# ALU_Connector.net
KiCad netlist of a schematic drawn in Altium Designer
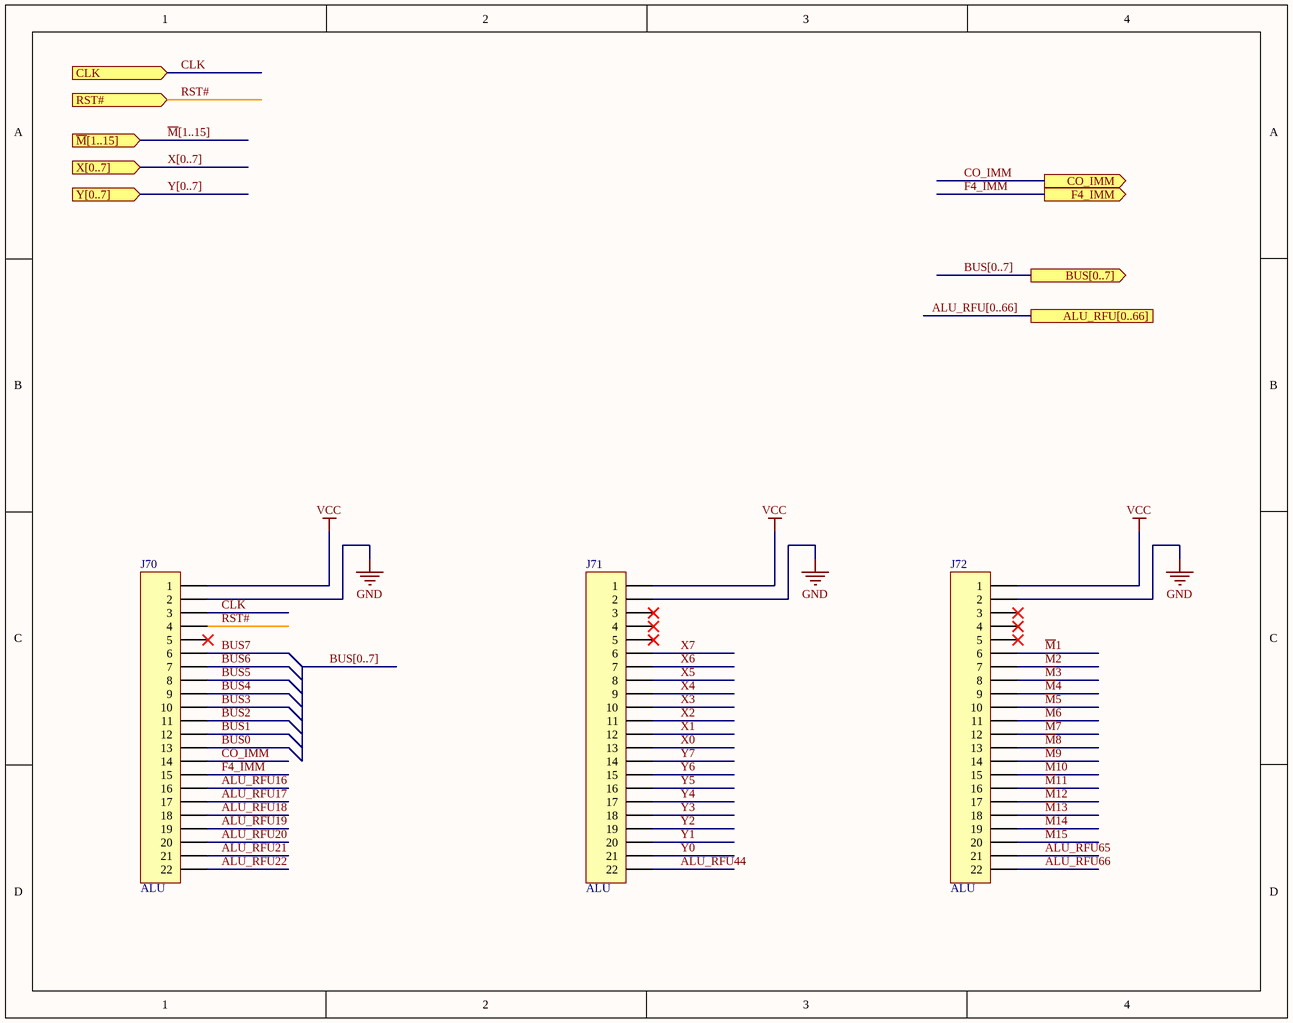
[diagram p0: ALU Connector.SchDoc]

(export (version "E")
  (design (tool "Eeschema 10.0.6"))
  (components
    (comp (ref "J70")
      (value "ALU")
      (footprint "HDR1X22")
      (description "Header, 22-Pin")
      (fields (field (name "PUBLISHER") "Altium Limited"))
      (libsource (lib "Miscellaneous Connectors") (part "Header 22"))
    )
    (comp (ref "J71")
      (value "ALU")
      (footprint "HDR1X22")
      (description "Header, 22-Pin")
      (fields (field (name "PUBLISHER") "Altium Limited"))
      (libsource (lib "Miscellaneous Connectors") (part "Header 22"))
    )
    (comp (ref "J72")
      (value "ALU")
      (footprint "HDR1X22")
      (description "Header, 22-Pin")
      (fields (field (name "PUBLISHER") "Altium Limited"))
      (libsource (lib "Miscellaneous Connectors") (part "Header 22"))
    )
  )
  (nets
    (net (code "58") (name "/ALU_RFU16") (class "Default")
      (node (ref "J70") (pin "16") (pinfunction "16_16") (pintype "passive"))
    )
    (net (code "59") (name "/ALU_RFU17") (class "Default")
      (node (ref "J70") (pin "17") (pinfunction "17_17") (pintype "passive"))
    )
    (net (code "60") (name "/ALU_RFU18") (class "Default")
      (node (ref "J70") (pin "18") (pinfunction "18_18") (pintype "passive"))
    )
    (net (code "61") (name "/ALU_RFU19") (class "Default")
      (node (ref "J70") (pin "19") (pinfunction "19_19") (pintype "passive"))
    )
    (net (code "62") (name "/ALU_RFU20") (class "Default")
      (node (ref "J70") (pin "20") (pinfunction "20_20") (pintype "passive"))
    )
    (net (code "63") (name "/ALU_RFU21") (class "Default")
      (node (ref "J70") (pin "21") (pinfunction "21_21") (pintype "passive"))
    )
    (net (code "64") (name "/ALU_RFU22") (class "Default")
      (node (ref "J70") (pin "22") (pinfunction "22_22") (pintype "passive"))
    )
    (net (code "65") (name "/ALU_RFU44") (class "Default")
      (node (ref "J71") (pin "22") (pinfunction "22_22") (pintype "passive"))
    )
    (net (code "66") (name "/ALU_RFU65") (class "Default")
      (node (ref "J72") (pin "21") (pinfunction "21_21") (pintype "passive"))
    )
    (net (code "67") (name "/ALU_RFU66") (class "Default")
      (node (ref "J72") (pin "22") (pinfunction "22_22") (pintype "passive"))
    )
    (net (code "69") (name "/BUS0") (class "Default")
      (node (ref "J70") (pin "13") (pinfunction "13_13") (pintype "passive"))
    )
    (net (code "70") (name "/BUS1") (class "Default")
      (node (ref "J70") (pin "12") (pinfunction "12_12") (pintype "passive"))
    )
    (net (code "71") (name "/BUS2") (class "Default")
      (node (ref "J70") (pin "11") (pinfunction "11_11") (pintype "passive"))
    )
    (net (code "72") (name "/BUS3") (class "Default")
      (node (ref "J70") (pin "10") (pinfunction "10_10") (pintype "passive"))
    )
    (net (code "73") (name "/BUS4") (class "Default")
      (node (ref "J70") (pin "9") (pinfunction "9_9") (pintype "passive"))
    )
    (net (code "74") (name "/BUS5") (class "Default")
      (node (ref "J70") (pin "8") (pinfunction "8_8") (pintype "passive"))
    )
    (net (code "75") (name "/BUS6") (class "Default")
      (node (ref "J70") (pin "7") (pinfunction "7_7") (pintype "passive"))
    )
    (net (code "76") (name "/BUS7") (class "Default")
      (node (ref "J70") (pin "6") (pinfunction "6_6") (pintype "passive"))
    )
    (net (code "78") (name "/CLK") (class "Default")
      (node (ref "J70") (pin "3") (pinfunction "3_3") (pintype "passive"))
    )
    (net (code "79") (name "/CO_IMM") (class "Default")
      (node (ref "J70") (pin "14") (pinfunction "14_14") (pintype "passive"))
    )
    (net (code "80") (name "/F4_IMM") (class "Default")
      (node (ref "J70") (pin "15") (pinfunction "15_15") (pintype "passive"))
    )
    (net (code "81") (name "/RST#") (class "Default")
      (node (ref "J70") (pin "4") (pinfunction "4_4") (pintype "passive"))
    )
    (net (code "82") (name "/X0") (class "Default")
      (node (ref "J71") (pin "13") (pinfunction "13_13") (pintype "passive"))
    )
    (net (code "83") (name "/X1") (class "Default")
      (node (ref "J71") (pin "12") (pinfunction "12_12") (pintype "passive"))
    )
    (net (code "84") (name "/X2") (class "Default")
      (node (ref "J71") (pin "11") (pinfunction "11_11") (pintype "passive"))
    )
    (net (code "85") (name "/X3") (class "Default")
      (node (ref "J71") (pin "10") (pinfunction "10_10") (pintype "passive"))
    )
    (net (code "86") (name "/X4") (class "Default")
      (node (ref "J71") (pin "9") (pinfunction "9_9") (pintype "passive"))
    )
    (net (code "87") (name "/X5") (class "Default")
      (node (ref "J71") (pin "8") (pinfunction "8_8") (pintype "passive"))
    )
    (net (code "88") (name "/X6") (class "Default")
      (node (ref "J71") (pin "7") (pinfunction "7_7") (pintype "passive"))
    )
    (net (code "89") (name "/X7") (class "Default")
      (node (ref "J71") (pin "6") (pinfunction "6_6") (pintype "passive"))
    )
    (net (code "91") (name "/Y0") (class "Default")
      (node (ref "J71") (pin "21") (pinfunction "21_21") (pintype "passive"))
    )
    (net (code "92") (name "/Y1") (class "Default")
      (node (ref "J71") (pin "20") (pinfunction "20_20") (pintype "passive"))
    )
    (net (code "93") (name "/Y2") (class "Default")
      (node (ref "J71") (pin "19") (pinfunction "19_19") (pintype "passive"))
    )
    (net (code "94") (name "/Y3") (class "Default")
      (node (ref "J71") (pin "18") (pinfunction "18_18") (pintype "passive"))
    )
    (net (code "95") (name "/Y4") (class "Default")
      (node (ref "J71") (pin "17") (pinfunction "17_17") (pintype "passive"))
    )
    (net (code "96") (name "/Y5") (class "Default")
      (node (ref "J71") (pin "16") (pinfunction "16_16") (pintype "passive"))
    )
    (net (code "97") (name "/Y6") (class "Default")
      (node (ref "J71") (pin "15") (pinfunction "15_15") (pintype "passive"))
    )
    (net (code "98") (name "/Y7") (class "Default")
      (node (ref "J71") (pin "14") (pinfunction "14_14") (pintype "passive"))
    )
    (net (code "100") (name "/~{M}1") (class "Default")
      (node (ref "J72") (pin "6") (pinfunction "6_6") (pintype "passive"))
    )
    (net (code "101") (name "/~{M}2") (class "Default")
      (node (ref "J72") (pin "7") (pinfunction "7_7") (pintype "passive"))
    )
    (net (code "102") (name "/~{M}3") (class "Default")
      (node (ref "J72") (pin "8") (pinfunction "8_8") (pintype "passive"))
    )
    (net (code "103") (name "/~{M}4") (class "Default")
      (node (ref "J72") (pin "9") (pinfunction "9_9") (pintype "passive"))
    )
    (net (code "104") (name "/~{M}5") (class "Default")
      (node (ref "J72") (pin "10") (pinfunction "10_10") (pintype "passive"))
    )
    (net (code "105") (name "/~{M}6") (class "Default")
      (node (ref "J72") (pin "11") (pinfunction "11_11") (pintype "passive"))
    )
    (net (code "106") (name "/~{M}7") (class "Default")
      (node (ref "J72") (pin "12") (pinfunction "12_12") (pintype "passive"))
    )
    (net (code "107") (name "/~{M}8") (class "Default")
      (node (ref "J72") (pin "13") (pinfunction "13_13") (pintype "passive"))
    )
    (net (code "108") (name "/~{M}9") (class "Default")
      (node (ref "J72") (pin "14") (pinfunction "14_14") (pintype "passive"))
    )
    (net (code "109") (name "/~{M}10") (class "Default")
      (node (ref "J72") (pin "15") (pinfunction "15_15") (pintype "passive"))
    )
    (net (code "110") (name "/~{M}11") (class "Default")
      (node (ref "J72") (pin "16") (pinfunction "16_16") (pintype "passive"))
    )
    (net (code "111") (name "/~{M}12") (class "Default")
      (node (ref "J72") (pin "17") (pinfunction "17_17") (pintype "passive"))
    )
    (net (code "112") (name "/~{M}13") (class "Default")
      (node (ref "J72") (pin "18") (pinfunction "18_18") (pintype "passive"))
    )
    (net (code "113") (name "/~{M}14") (class "Default")
      (node (ref "J72") (pin "19") (pinfunction "19_19") (pintype "passive"))
    )
    (net (code "114") (name "/~{M}15") (class "Default")
      (node (ref "J72") (pin "20") (pinfunction "20_20") (pintype "passive"))
    )
    (net (code "116") (name "GND") (class "Default")
      (node (ref "J70") (pin "2") (pinfunction "2_2") (pintype "passive"))
      (node (ref "J71") (pin "2") (pinfunction "2_2") (pintype "passive"))
      (node (ref "J72") (pin "2") (pinfunction "2_2") (pintype "passive"))
    )
    (net (code "117") (name "VCC") (class "Default")
      (node (ref "J70") (pin "1") (pinfunction "1_1") (pintype "passive"))
      (node (ref "J71") (pin "1") (pinfunction "1_1") (pintype "passive"))
      (node (ref "J72") (pin "1") (pinfunction "1_1") (pintype "passive"))
    )
    (net (code "118") (name "unconnected-(J70-Pad5)") (class "Default")
      (node (ref "J70") (pin "5") (pinfunction "5_5") (pintype "passive+no_connect"))
    )
    (net (code "119") (name "unconnected-(J71-Pad3)") (class "Default")
      (node (ref "J71") (pin "3") (pinfunction "3_3") (pintype "passive+no_connect"))
    )
    (net (code "120") (name "unconnected-(J71-Pad4)") (class "Default")
      (node (ref "J71") (pin "4") (pinfunction "4_4") (pintype "passive+no_connect"))
    )
    (net (code "121") (name "unconnected-(J71-Pad5)") (class "Default")
      (node (ref "J71") (pin "5") (pinfunction "5_5") (pintype "passive+no_connect"))
    )
    (net (code "122") (name "unconnected-(J72-Pad3)") (class "Default")
      (node (ref "J72") (pin "3") (pinfunction "3_3") (pintype "passive+no_connect"))
    )
    (net (code "123") (name "unconnected-(J72-Pad4)") (class "Default")
      (node (ref "J72") (pin "4") (pinfunction "4_4") (pintype "passive+no_connect"))
    )
    (net (code "124") (name "unconnected-(J72-Pad5)") (class "Default")
      (node (ref "J72") (pin "5") (pinfunction "5_5") (pintype "passive+no_connect"))
    )
  )
)
